# Clock_Segment.net
KiCad netlist of a schematic drawn in Altium Designer
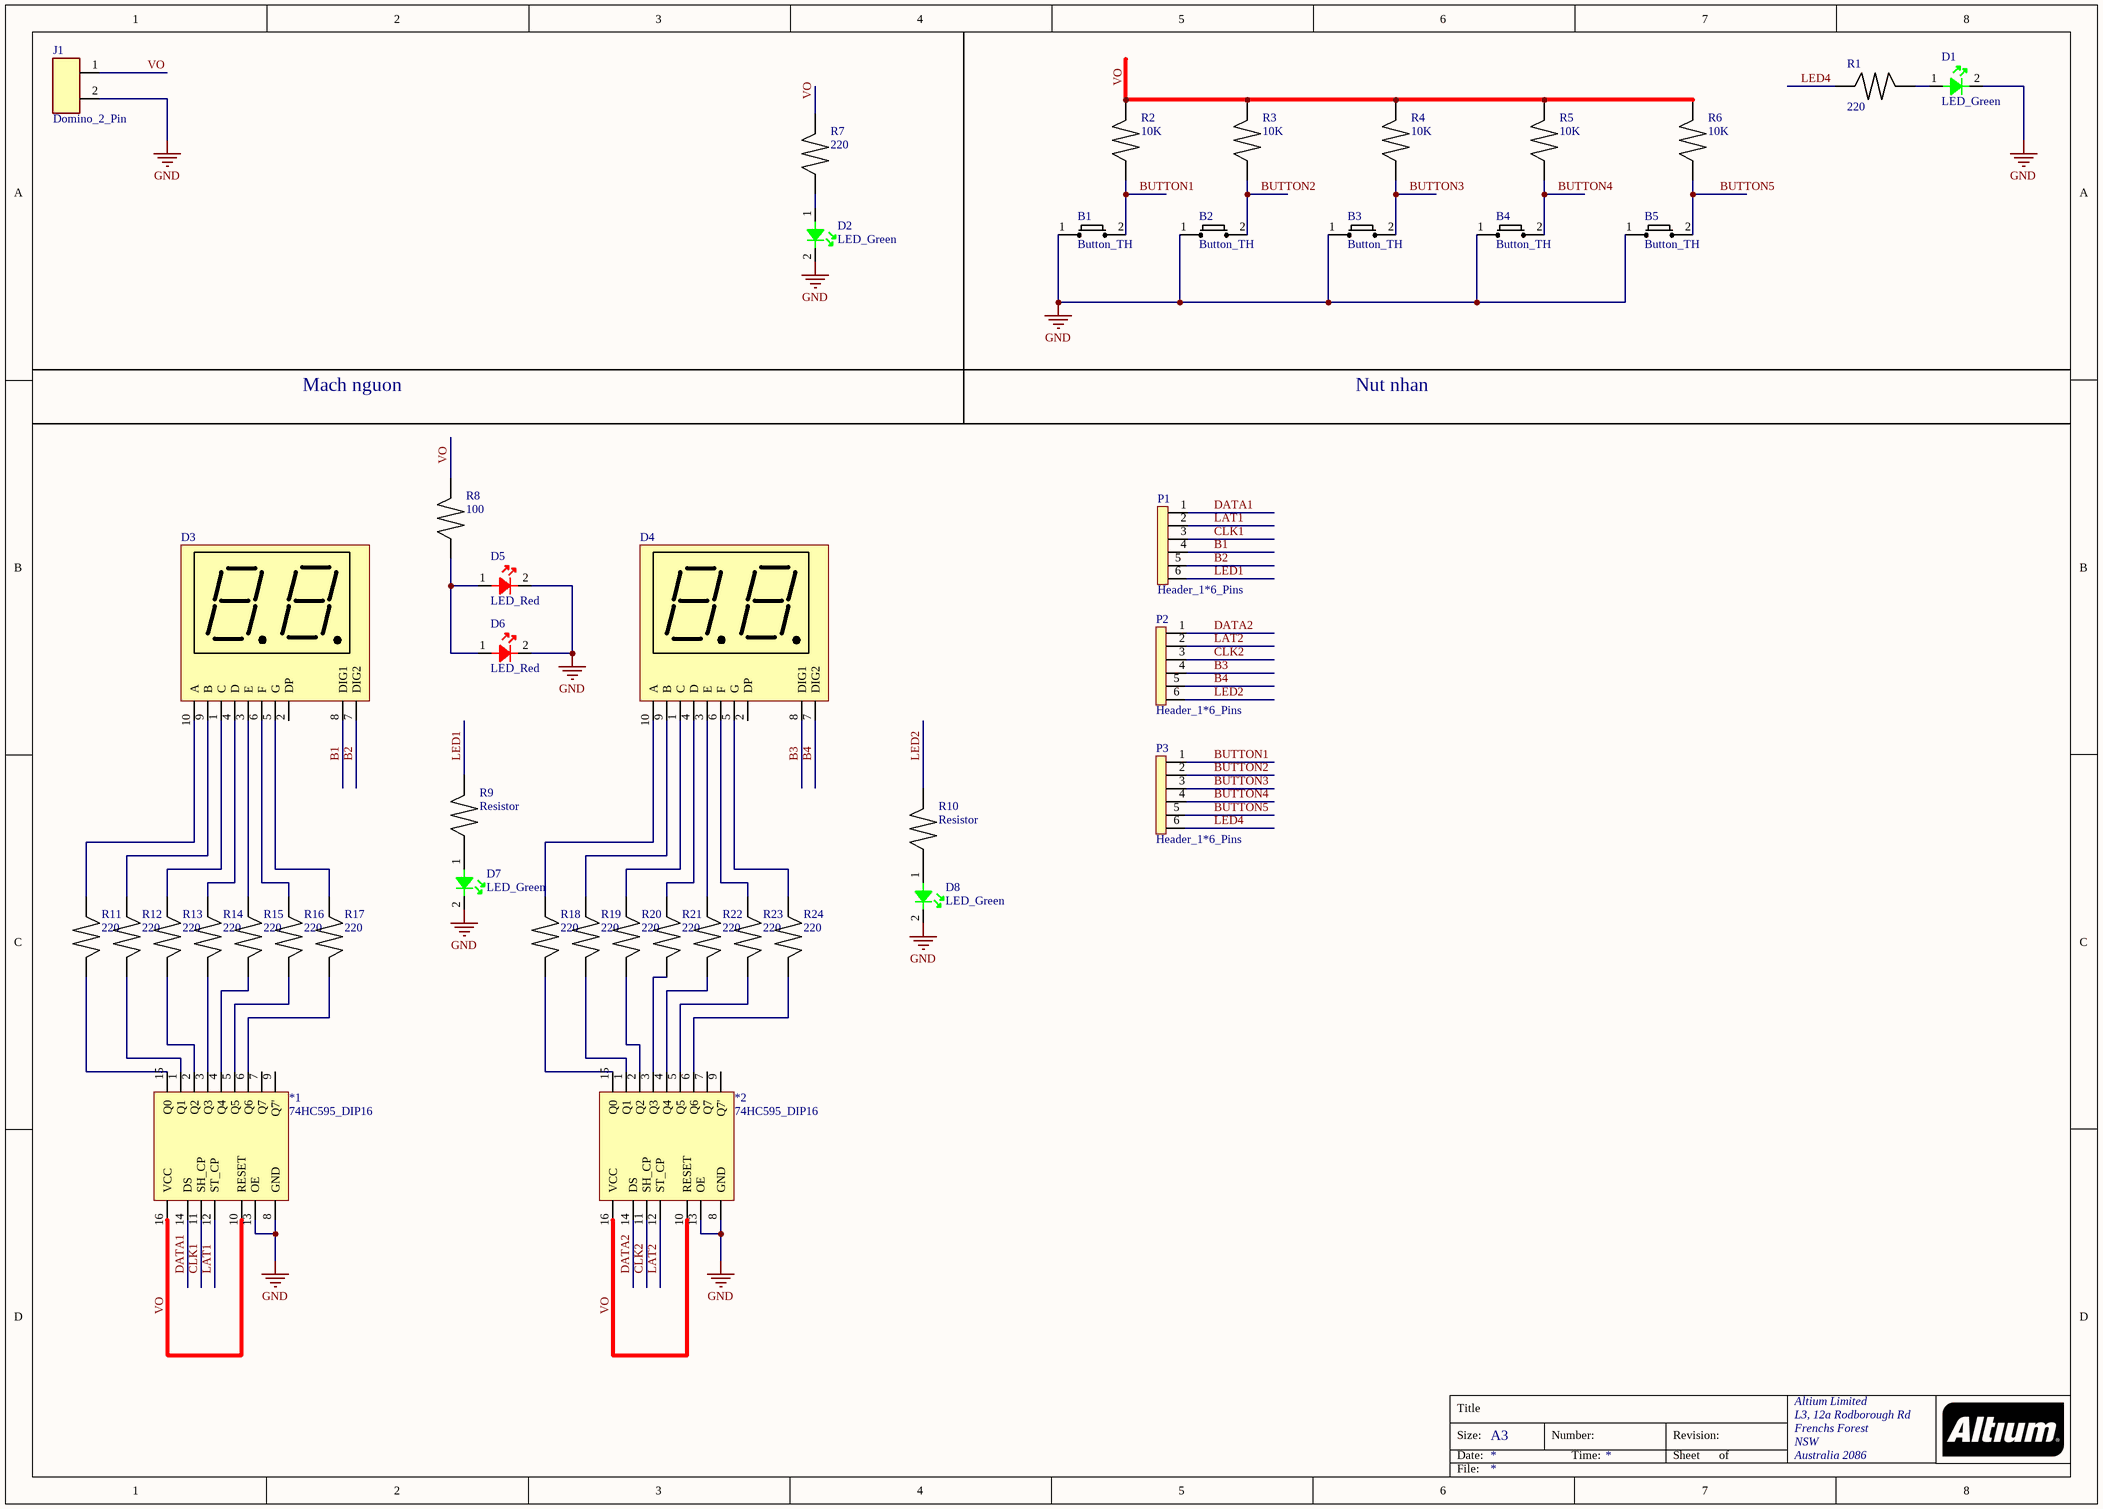
[diagram p0: Clock Segment.SchDoc]

(export (version "E")
  (design (tool "Eeschema 10.0.6"))
  (components
    (comp (ref "*1")
      (value "74HC595_DIP16")
      (footprint "Altium Lib:DIP_16")
      (libsource (lib "Altium Lib") (part "74HC595_DIP16"))
    )
    (comp (ref "*2")
      (value "74HC595_DIP16")
      (footprint "Altium Lib:DIP_16")
      (libsource (lib "Altium Lib") (part "74HC595_DIP16"))
    )
    (comp (ref "B1")
      (value "Button_TH")
      (footprint "Altium Lib:BUTTON_TH")
      (description "6x6mm, TH, 2 Pins")
      (libsource (lib "Altium Lib") (part "Button_TH"))
    )
    (comp (ref "B2")
      (value "Button_TH")
      (footprint "Altium Lib:BUTTON_TH")
      (description "6x6mm, TH, 2 Pins")
      (libsource (lib "Altium Lib") (part "Button_TH"))
    )
    (comp (ref "B3")
      (value "Button_TH")
      (footprint "Altium Lib:BUTTON_TH")
      (description "6x6mm, TH, 2 Pins")
      (libsource (lib "Altium Lib") (part "Button_TH"))
    )
    (comp (ref "B4")
      (value "Button_TH")
      (footprint "Altium Lib:BUTTON_TH")
      (description "6x6mm, TH, 2 Pins")
      (libsource (lib "Altium Lib") (part "Button_TH"))
    )
    (comp (ref "B5")
      (value "Button_TH")
      (footprint "Altium Lib:BUTTON_TH")
      (description "6x6mm, TH, 2 Pins")
      (libsource (lib "Altium Lib") (part "Button_TH"))
    )
    (comp (ref "D1")
      (value "LED_Green")
      (footprint "Altium Lib:LED_Green_TH_5mm")
      (libsource (lib "Altium Lib") (part "LED_Green"))
    )
    (comp (ref "D2")
      (value "LED_Green")
      (footprint "Altium Lib:LED_Green_TH_5mm")
      (libsource (lib "Altium Lib") (part "LED_Green"))
    )
    (comp (ref "D3")
      (value "7_Segment_2_Figures")
      (footprint "Altium Lib:5621BS")
      (libsource (lib "Altium Lib") (part "7_Segment_2_Figures"))
    )
    (comp (ref "D4")
      (value "7_Segment_2_Figures")
      (footprint "Altium Lib:5621BS")
      (libsource (lib "Altium Lib") (part "7_Segment_2_Figures"))
    )
    (comp (ref "D5")
      (value "LED_Red")
      (footprint "Altium Lib:LED_Red_TH_5mm")
      (libsource (lib "Altium Lib") (part "LED_Red"))
    )
    (comp (ref "D6")
      (value "LED_Red")
      (footprint "Altium Lib:LED_Red_TH_5mm")
      (libsource (lib "Altium Lib") (part "LED_Red"))
    )
    (comp (ref "D7")
      (value "LED_Green")
      (footprint "Altium Lib:LED_Green_TH_5mm")
      (libsource (lib "Altium Lib") (part "LED_Green"))
    )
    (comp (ref "D8")
      (value "LED_Green")
      (footprint "Altium Lib:LED_Green_TH_5mm")
      (libsource (lib "Altium Lib") (part "LED_Green"))
    )
    (comp (ref "J1")
      (value "Domino_2_Pin")
      (footprint "Altium Lib:domino_2_pin")
      (libsource (lib "Altium Lib") (part "Domino_2_Pin"))
    )
    (comp (ref "P1")
      (value "Header_1*6_Pins")
      (footprint "Altium Lib:HDR_M_6_Pins_2.54")
      (libsource (lib "Altium Lib") (part "Header_1*6_Pins"))
    )
    (comp (ref "P2")
      (value "Header_1*6_Pins")
      (footprint "Altium Lib:HDR_M_6_Pins_2.54")
      (libsource (lib "Altium Lib") (part "Header_1*6_Pins"))
    )
    (comp (ref "P3")
      (value "Header_1*6_Pins")
      (footprint "Altium Lib:HDR_M_6_Pins_2.54")
      (libsource (lib "Altium Lib") (part "Header_1*6_Pins"))
    )
    (comp (ref "R1")
      (value "220")
      (footprint "Altium Lib:Resistor_TH_1/4W")
      (description "Resistor_TH_1/4W")
      (libsource (lib "Altium Lib") (part "Resistor"))
    )
    (comp (ref "R2")
      (value "10K")
      (footprint "Altium Lib:Resistor_TH_1/4W")
      (description "Resistor_TH_1/4W")
      (libsource (lib "Altium Lib") (part "Resistor"))
    )
    (comp (ref "R3")
      (value "10K")
      (footprint "Altium Lib:Resistor_TH_1/4W")
      (description "Resistor_TH_1/4W")
      (libsource (lib "Altium Lib") (part "Resistor"))
    )
    (comp (ref "R4")
      (value "10K")
      (footprint "Altium Lib:Resistor_TH_1/4W")
      (description "Resistor_TH_1/4W")
      (libsource (lib "Altium Lib") (part "Resistor"))
    )
    (comp (ref "R5")
      (value "10K")
      (footprint "Altium Lib:Resistor_TH_1/4W")
      (description "Resistor_TH_1/4W")
      (libsource (lib "Altium Lib") (part "Resistor"))
    )
    (comp (ref "R6")
      (value "10K")
      (footprint "Altium Lib:Resistor_TH_1/4W")
      (description "Resistor_TH_1/4W")
      (libsource (lib "Altium Lib") (part "Resistor"))
    )
    (comp (ref "R7")
      (value "220")
      (footprint "Altium Lib:Resistor_TH_1/4W")
      (description "Resistor_TH_1/4W")
      (libsource (lib "Altium Lib") (part "Resistor"))
    )
    (comp (ref "R8")
      (value "100")
      (footprint "Altium Lib:Resistor_TH_1/4W")
      (description "Resistor_TH_1/4W")
      (libsource (lib "Altium Lib") (part "Resistor"))
    )
    (comp (ref "R9")
      (value "Resistor")
      (footprint "Altium Lib:Resistor_TH_1/4W")
      (description "Resistor_TH_1/4W")
      (libsource (lib "Altium Lib") (part "Resistor"))
    )
    (comp (ref "R10")
      (value "Resistor")
      (footprint "Altium Lib:Resistor_TH_1/4W")
      (description "Resistor_TH_1/4W")
      (libsource (lib "Altium Lib") (part "Resistor"))
    )
    (comp (ref "R11")
      (value "220")
      (footprint "Altium Lib:Resistor_TH_1/4W")
      (description "Resistor_TH_1/4W")
      (libsource (lib "Altium Lib") (part "Resistor"))
    )
    (comp (ref "R12")
      (value "220")
      (footprint "Altium Lib:Resistor_TH_1/4W")
      (description "Resistor_TH_1/4W")
      (libsource (lib "Altium Lib") (part "Resistor"))
    )
    (comp (ref "R13")
      (value "220")
      (footprint "Altium Lib:Resistor_TH_1/4W")
      (description "Resistor_TH_1/4W")
      (libsource (lib "Altium Lib") (part "Resistor"))
    )
    (comp (ref "R14")
      (value "220")
      (footprint "Altium Lib:Resistor_TH_1/4W")
      (description "Resistor_TH_1/4W")
      (libsource (lib "Altium Lib") (part "Resistor"))
    )
    (comp (ref "R15")
      (value "220")
      (footprint "Altium Lib:Resistor_TH_1/4W")
      (description "Resistor_TH_1/4W")
      (libsource (lib "Altium Lib") (part "Resistor"))
    )
    (comp (ref "R16")
      (value "220")
      (footprint "Altium Lib:Resistor_TH_1/4W")
      (description "Resistor_TH_1/4W")
      (libsource (lib "Altium Lib") (part "Resistor"))
    )
    (comp (ref "R17")
      (value "220")
      (footprint "Altium Lib:Resistor_TH_1/4W")
      (description "Resistor_TH_1/4W")
      (libsource (lib "Altium Lib") (part "Resistor"))
    )
    (comp (ref "R18")
      (value "220")
      (footprint "Altium Lib:Resistor_TH_1/4W")
      (description "Resistor_TH_1/4W")
      (libsource (lib "Altium Lib") (part "Resistor"))
    )
    (comp (ref "R19")
      (value "220")
      (footprint "Altium Lib:Resistor_TH_1/4W")
      (description "Resistor_TH_1/4W")
      (libsource (lib "Altium Lib") (part "Resistor"))
    )
    (comp (ref "R20")
      (value "220")
      (footprint "Altium Lib:Resistor_TH_1/4W")
      (description "Resistor_TH_1/4W")
      (libsource (lib "Altium Lib") (part "Resistor"))
    )
    (comp (ref "R21")
      (value "220")
      (footprint "Altium Lib:Resistor_TH_1/4W")
      (description "Resistor_TH_1/4W")
      (libsource (lib "Altium Lib") (part "Resistor"))
    )
    (comp (ref "R22")
      (value "220")
      (footprint "Altium Lib:Resistor_TH_1/4W")
      (description "Resistor_TH_1/4W")
      (libsource (lib "Altium Lib") (part "Resistor"))
    )
    (comp (ref "R23")
      (value "220")
      (footprint "Altium Lib:Resistor_TH_1/4W")
      (description "Resistor_TH_1/4W")
      (libsource (lib "Altium Lib") (part "Resistor"))
    )
    (comp (ref "R24")
      (value "220")
      (footprint "Altium Lib:Resistor_TH_1/4W")
      (description "Resistor_TH_1/4W")
      (libsource (lib "Altium Lib") (part "Resistor"))
    )
  )
  (nets
    (net (code "1") (name "/B1") (class "Default")
      (node (ref "D3") (pin "8") (pinfunction "DIG1_8") (pintype "passive"))
      (node (ref "P1") (pin "4") (pinfunction "4_4") (pintype "passive"))
    )
    (net (code "2") (name "/B2") (class "Default")
      (node (ref "D3") (pin "7") (pinfunction "DIG2_7") (pintype "passive"))
      (node (ref "P1") (pin "5") (pinfunction "3.81_5") (pintype "passive"))
    )
    (net (code "3") (name "/B3") (class "Default")
      (node (ref "D4") (pin "8") (pinfunction "DIG1_8") (pintype "passive"))
      (node (ref "P2") (pin "4") (pinfunction "4_4") (pintype "passive"))
    )
    (net (code "4") (name "/B4") (class "Default")
      (node (ref "D4") (pin "7") (pinfunction "DIG2_7") (pintype "passive"))
      (node (ref "P2") (pin "5") (pinfunction "3.81_5") (pintype "passive"))
    )
    (net (code "5") (name "/BUTTON1") (class "Default")
      (node (ref "B1") (pin "2") (pinfunction "2_2") (pintype "passive"))
      (node (ref "P3") (pin "1") (pinfunction "1_1") (pintype "passive"))
      (node (ref "R2") (pin "1") (pinfunction "1_1") (pintype "passive"))
    )
    (net (code "6") (name "/BUTTON2") (class "Default")
      (node (ref "B2") (pin "2") (pinfunction "2_2") (pintype "passive"))
      (node (ref "P3") (pin "2") (pinfunction "2_2") (pintype "passive"))
      (node (ref "R3") (pin "1") (pinfunction "1_1") (pintype "passive"))
    )
    (net (code "7") (name "/BUTTON3") (class "Default")
      (node (ref "B3") (pin "2") (pinfunction "2_2") (pintype "passive"))
      (node (ref "P3") (pin "3") (pinfunction "3_3") (pintype "passive"))
      (node (ref "R4") (pin "1") (pinfunction "1_1") (pintype "passive"))
    )
    (net (code "8") (name "/BUTTON4") (class "Default")
      (node (ref "B4") (pin "2") (pinfunction "2_2") (pintype "passive"))
      (node (ref "P3") (pin "4") (pinfunction "4_4") (pintype "passive"))
      (node (ref "R5") (pin "1") (pinfunction "1_1") (pintype "passive"))
    )
    (net (code "9") (name "/BUTTON5") (class "Default")
      (node (ref "B5") (pin "2") (pinfunction "2_2") (pintype "passive"))
      (node (ref "P3") (pin "5") (pinfunction "3.81_5") (pintype "passive"))
      (node (ref "R6") (pin "1") (pinfunction "1_1") (pintype "passive"))
    )
    (net (code "10") (name "/CLK1") (class "Default")
      (node (ref "*1") (pin "11") (pinfunction "SH_CP_11") (pintype "passive"))
      (node (ref "P1") (pin "3") (pinfunction "3_3") (pintype "passive"))
    )
    (net (code "11") (name "/CLK2") (class "Default")
      (node (ref "*2") (pin "11") (pinfunction "SH_CP_11") (pintype "passive"))
      (node (ref "P2") (pin "3") (pinfunction "3_3") (pintype "passive"))
    )
    (net (code "12") (name "/DATA1") (class "Default")
      (node (ref "*1") (pin "14") (pinfunction "DS_14") (pintype "passive"))
      (node (ref "P1") (pin "1") (pinfunction "1_1") (pintype "passive"))
    )
    (net (code "13") (name "/DATA2") (class "Default")
      (node (ref "*2") (pin "14") (pinfunction "DS_14") (pintype "passive"))
      (node (ref "P2") (pin "1") (pinfunction "1_1") (pintype "passive"))
    )
    (net (code "14") (name "/LAT1") (class "Default")
      (node (ref "*1") (pin "12") (pinfunction "ST_CP_12") (pintype "passive"))
      (node (ref "P1") (pin "2") (pinfunction "2_2") (pintype "passive"))
    )
    (net (code "15") (name "/LAT2") (class "Default")
      (node (ref "*2") (pin "12") (pinfunction "ST_CP_12") (pintype "passive"))
      (node (ref "P2") (pin "2") (pinfunction "2_2") (pintype "passive"))
    )
    (net (code "16") (name "/LED1") (class "Default")
      (node (ref "P1") (pin "6") (pinfunction "3.81_6") (pintype "passive"))
      (node (ref "R9") (pin "2") (pinfunction "2_2") (pintype "passive"))
    )
    (net (code "17") (name "/LED2") (class "Default")
      (node (ref "P2") (pin "6") (pinfunction "3.81_6") (pintype "passive"))
      (node (ref "R10") (pin "2") (pinfunction "2_2") (pintype "passive"))
    )
    (net (code "18") (name "/LED4") (class "Default")
      (node (ref "P3") (pin "6") (pinfunction "3.81_6") (pintype "passive"))
      (node (ref "R1") (pin "1") (pinfunction "1_1") (pintype "passive"))
    )
    (net (code "19") (name "/VO") (class "Default")
      (node (ref "*1") (pin "10") (pinfunction "RESET_10") (pintype "passive"))
      (node (ref "*1") (pin "16") (pinfunction "VCC_16") (pintype "passive"))
      (node (ref "*2") (pin "10") (pinfunction "RESET_10") (pintype "passive"))
      (node (ref "*2") (pin "16") (pinfunction "VCC_16") (pintype "passive"))
      (node (ref "J1") (pin "1") (pinfunction "1_1") (pintype "passive"))
      (node (ref "R2") (pin "2") (pinfunction "2_2") (pintype "passive"))
      (node (ref "R3") (pin "2") (pinfunction "2_2") (pintype "passive"))
      (node (ref "R4") (pin "2") (pinfunction "2_2") (pintype "passive"))
      (node (ref "R5") (pin "2") (pinfunction "2_2") (pintype "passive"))
      (node (ref "R6") (pin "2") (pinfunction "2_2") (pintype "passive"))
      (node (ref "R7") (pin "2") (pinfunction "2_2") (pintype "passive"))
      (node (ref "R8") (pin "2") (pinfunction "2_2") (pintype "passive"))
    )
    (net (code "20") (name "GND") (class "Default")
      (node (ref "*1") (pin "13") (pinfunction "OE_13") (pintype "passive"))
      (node (ref "*1") (pin "8") (pinfunction "GND_8") (pintype "passive"))
      (node (ref "*2") (pin "13") (pinfunction "OE_13") (pintype "passive"))
      (node (ref "*2") (pin "8") (pinfunction "GND_8") (pintype "passive"))
      (node (ref "B1") (pin "1") (pinfunction "1_1") (pintype "passive"))
      (node (ref "B2") (pin "1") (pinfunction "1_1") (pintype "passive"))
      (node (ref "B3") (pin "1") (pinfunction "1_1") (pintype "passive"))
      (node (ref "B4") (pin "1") (pinfunction "1_1") (pintype "passive"))
      (node (ref "B5") (pin "1") (pinfunction "1_1") (pintype "passive"))
      (node (ref "D1") (pin "2") (pinfunction "2_2") (pintype "passive"))
      (node (ref "D2") (pin "2") (pinfunction "2_2") (pintype "passive"))
      (node (ref "D5") (pin "2") (pinfunction "2_2") (pintype "passive"))
      (node (ref "D6") (pin "2") (pinfunction "2_2") (pintype "passive"))
      (node (ref "D7") (pin "2") (pinfunction "2_2") (pintype "passive"))
      (node (ref "D8") (pin "2") (pinfunction "2_2") (pintype "passive"))
      (node (ref "J1") (pin "2") (pinfunction "2_2") (pintype "passive"))
    )
    (net (code "21") (name "Net-(*1-Q0)") (class "Default")
      (node (ref "*1") (pin "15") (pinfunction "Q0_15") (pintype "passive"))
      (node (ref "R11") (pin "2") (pinfunction "2_2") (pintype "passive"))
    )
    (net (code "22") (name "Net-(*1-Q1)") (class "Default")
      (node (ref "*1") (pin "1") (pinfunction "Q1_1") (pintype "passive"))
      (node (ref "R12") (pin "2") (pinfunction "2_2") (pintype "passive"))
    )
    (net (code "23") (name "Net-(*1-Q2)") (class "Default")
      (node (ref "*1") (pin "2") (pinfunction "Q2_2") (pintype "passive"))
      (node (ref "R13") (pin "2") (pinfunction "2_2") (pintype "passive"))
    )
    (net (code "24") (name "Net-(*1-Q3)") (class "Default")
      (node (ref "*1") (pin "3") (pinfunction "Q3_3") (pintype "passive"))
      (node (ref "R14") (pin "2") (pinfunction "2_2") (pintype "passive"))
    )
    (net (code "25") (name "Net-(*1-Q4)") (class "Default")
      (node (ref "*1") (pin "4") (pinfunction "Q4_4") (pintype "passive"))
      (node (ref "R15") (pin "2") (pinfunction "2_2") (pintype "passive"))
    )
    (net (code "26") (name "Net-(*1-Q5)") (class "Default")
      (node (ref "*1") (pin "5") (pinfunction "Q5_5") (pintype "passive"))
      (node (ref "R16") (pin "2") (pinfunction "2_2") (pintype "passive"))
    )
    (net (code "27") (name "Net-(*1-Q6)") (class "Default")
      (node (ref "*1") (pin "6") (pinfunction "Q6_6") (pintype "passive"))
      (node (ref "R17") (pin "2") (pinfunction "2_2") (pintype "passive"))
    )
    (net (code "28") (name "Net-(*2-Q0)") (class "Default")
      (node (ref "*2") (pin "15") (pinfunction "Q0_15") (pintype "passive"))
      (node (ref "R18") (pin "2") (pinfunction "2_2") (pintype "passive"))
    )
    (net (code "29") (name "Net-(*2-Q1)") (class "Default")
      (node (ref "*2") (pin "1") (pinfunction "Q1_1") (pintype "passive"))
      (node (ref "R19") (pin "2") (pinfunction "2_2") (pintype "passive"))
    )
    (net (code "30") (name "Net-(*2-Q2)") (class "Default")
      (node (ref "*2") (pin "2") (pinfunction "Q2_2") (pintype "passive"))
      (node (ref "R20") (pin "2") (pinfunction "2_2") (pintype "passive"))
    )
    (net (code "31") (name "Net-(*2-Q3)") (class "Default")
      (node (ref "*2") (pin "3") (pinfunction "Q3_3") (pintype "passive"))
      (node (ref "R21") (pin "2") (pinfunction "2_2") (pintype "passive"))
    )
    (net (code "32") (name "Net-(*2-Q4)") (class "Default")
      (node (ref "*2") (pin "4") (pinfunction "Q4_4") (pintype "passive"))
      (node (ref "R22") (pin "2") (pinfunction "2_2") (pintype "passive"))
    )
    (net (code "33") (name "Net-(*2-Q5)") (class "Default")
      (node (ref "*2") (pin "5") (pinfunction "Q5_5") (pintype "passive"))
      (node (ref "R23") (pin "2") (pinfunction "2_2") (pintype "passive"))
    )
    (net (code "34") (name "Net-(*2-Q6)") (class "Default")
      (node (ref "*2") (pin "6") (pinfunction "Q6_6") (pintype "passive"))
      (node (ref "R24") (pin "2") (pinfunction "2_2") (pintype "passive"))
    )
    (net (code "35") (name "Net-(D1-Pad1)") (class "Default")
      (node (ref "D1") (pin "1") (pinfunction "1_1") (pintype "passive"))
      (node (ref "R1") (pin "2") (pinfunction "2_2") (pintype "passive"))
    )
    (net (code "36") (name "Net-(D2-Pad1)") (class "Default")
      (node (ref "D2") (pin "1") (pinfunction "1_1") (pintype "passive"))
      (node (ref "R7") (pin "1") (pinfunction "1_1") (pintype "passive"))
    )
    (net (code "37") (name "Net-(D3-A)") (class "Default")
      (node (ref "D3") (pin "10") (pinfunction "A_10") (pintype "passive"))
      (node (ref "R11") (pin "1") (pinfunction "1_1") (pintype "passive"))
    )
    (net (code "38") (name "Net-(D3-B)") (class "Default")
      (node (ref "D3") (pin "9") (pinfunction "B_9") (pintype "passive"))
      (node (ref "R12") (pin "1") (pinfunction "1_1") (pintype "passive"))
    )
    (net (code "39") (name "Net-(D3-C)") (class "Default")
      (node (ref "D3") (pin "1") (pinfunction "C_1") (pintype "passive"))
      (node (ref "R13") (pin "1") (pinfunction "1_1") (pintype "passive"))
    )
    (net (code "40") (name "Net-(D3-D)") (class "Default")
      (node (ref "D3") (pin "4") (pinfunction "D_4") (pintype "passive"))
      (node (ref "R14") (pin "1") (pinfunction "1_1") (pintype "passive"))
    )
    (net (code "41") (name "Net-(D3-E)") (class "Default")
      (node (ref "D3") (pin "3") (pinfunction "E_3") (pintype "passive"))
      (node (ref "R15") (pin "1") (pinfunction "1_1") (pintype "passive"))
    )
    (net (code "42") (name "Net-(D3-F)") (class "Default")
      (node (ref "D3") (pin "6") (pinfunction "F_6") (pintype "passive"))
      (node (ref "R16") (pin "1") (pinfunction "1_1") (pintype "passive"))
    )
    (net (code "43") (name "Net-(D3-G)") (class "Default")
      (node (ref "D3") (pin "5") (pinfunction "G_5") (pintype "passive"))
      (node (ref "R17") (pin "1") (pinfunction "1_1") (pintype "passive"))
    )
    (net (code "44") (name "Net-(D4-A)") (class "Default")
      (node (ref "D4") (pin "10") (pinfunction "A_10") (pintype "passive"))
      (node (ref "R18") (pin "1") (pinfunction "1_1") (pintype "passive"))
    )
    (net (code "45") (name "Net-(D4-B)") (class "Default")
      (node (ref "D4") (pin "9") (pinfunction "B_9") (pintype "passive"))
      (node (ref "R19") (pin "1") (pinfunction "1_1") (pintype "passive"))
    )
    (net (code "46") (name "Net-(D4-C)") (class "Default")
      (node (ref "D4") (pin "1") (pinfunction "C_1") (pintype "passive"))
      (node (ref "R20") (pin "1") (pinfunction "1_1") (pintype "passive"))
    )
    (net (code "47") (name "Net-(D4-D)") (class "Default")
      (node (ref "D4") (pin "4") (pinfunction "D_4") (pintype "passive"))
      (node (ref "R21") (pin "1") (pinfunction "1_1") (pintype "passive"))
    )
    (net (code "48") (name "Net-(D4-E)") (class "Default")
      (node (ref "D4") (pin "3") (pinfunction "E_3") (pintype "passive"))
      (node (ref "R22") (pin "1") (pinfunction "1_1") (pintype "passive"))
    )
    (net (code "49") (name "Net-(D4-F)") (class "Default")
      (node (ref "D4") (pin "6") (pinfunction "F_6") (pintype "passive"))
      (node (ref "R23") (pin "1") (pinfunction "1_1") (pintype "passive"))
    )
    (net (code "50") (name "Net-(D4-G)") (class "Default")
      (node (ref "D4") (pin "5") (pinfunction "G_5") (pintype "passive"))
      (node (ref "R24") (pin "1") (pinfunction "1_1") (pintype "passive"))
    )
    (net (code "51") (name "Net-(D5-Pad1)") (class "Default")
      (node (ref "D5") (pin "1") (pinfunction "1_1") (pintype "passive"))
      (node (ref "D6") (pin "1") (pinfunction "1_1") (pintype "passive"))
      (node (ref "R8") (pin "1") (pinfunction "1_1") (pintype "passive"))
    )
    (net (code "52") (name "Net-(D7-Pad1)") (class "Default")
      (node (ref "D7") (pin "1") (pinfunction "1_1") (pintype "passive"))
      (node (ref "R9") (pin "1") (pinfunction "1_1") (pintype "passive"))
    )
    (net (code "53") (name "Net-(D8-Pad1)") (class "Default")
      (node (ref "D8") (pin "1") (pinfunction "1_1") (pintype "passive"))
      (node (ref "R10") (pin "1") (pinfunction "1_1") (pintype "passive"))
    )
    (net (code "54") (name "unconnected-(*1-Q7'-Pad9)") (class "Default")
      (node (ref "*1") (pin "9") (pinfunction "Q7'_9") (pintype "passive"))
    )
    (net (code "55") (name "unconnected-(*1-Q7-Pad7)") (class "Default")
      (node (ref "*1") (pin "7") (pinfunction "Q7_7") (pintype "passive"))
    )
    (net (code "56") (name "unconnected-(*2-Q7'-Pad9)") (class "Default")
      (node (ref "*2") (pin "9") (pinfunction "Q7'_9") (pintype "passive"))
    )
    (net (code "57") (name "unconnected-(*2-Q7-Pad7)") (class "Default")
      (node (ref "*2") (pin "7") (pinfunction "Q7_7") (pintype "passive"))
    )
    (net (code "58") (name "unconnected-(D3-DP-Pad2)") (class "Default")
      (node (ref "D3") (pin "2") (pinfunction "DP_2") (pintype "passive"))
    )
    (net (code "59") (name "unconnected-(D4-DP-Pad2)") (class "Default")
      (node (ref "D4") (pin "2") (pinfunction "DP_2") (pintype "passive"))
    )
  )
)
